# Pure_Keys_aec-pcb3-smd-inProgress.net
KiCad netlist of a schematic drawn in EAGLE
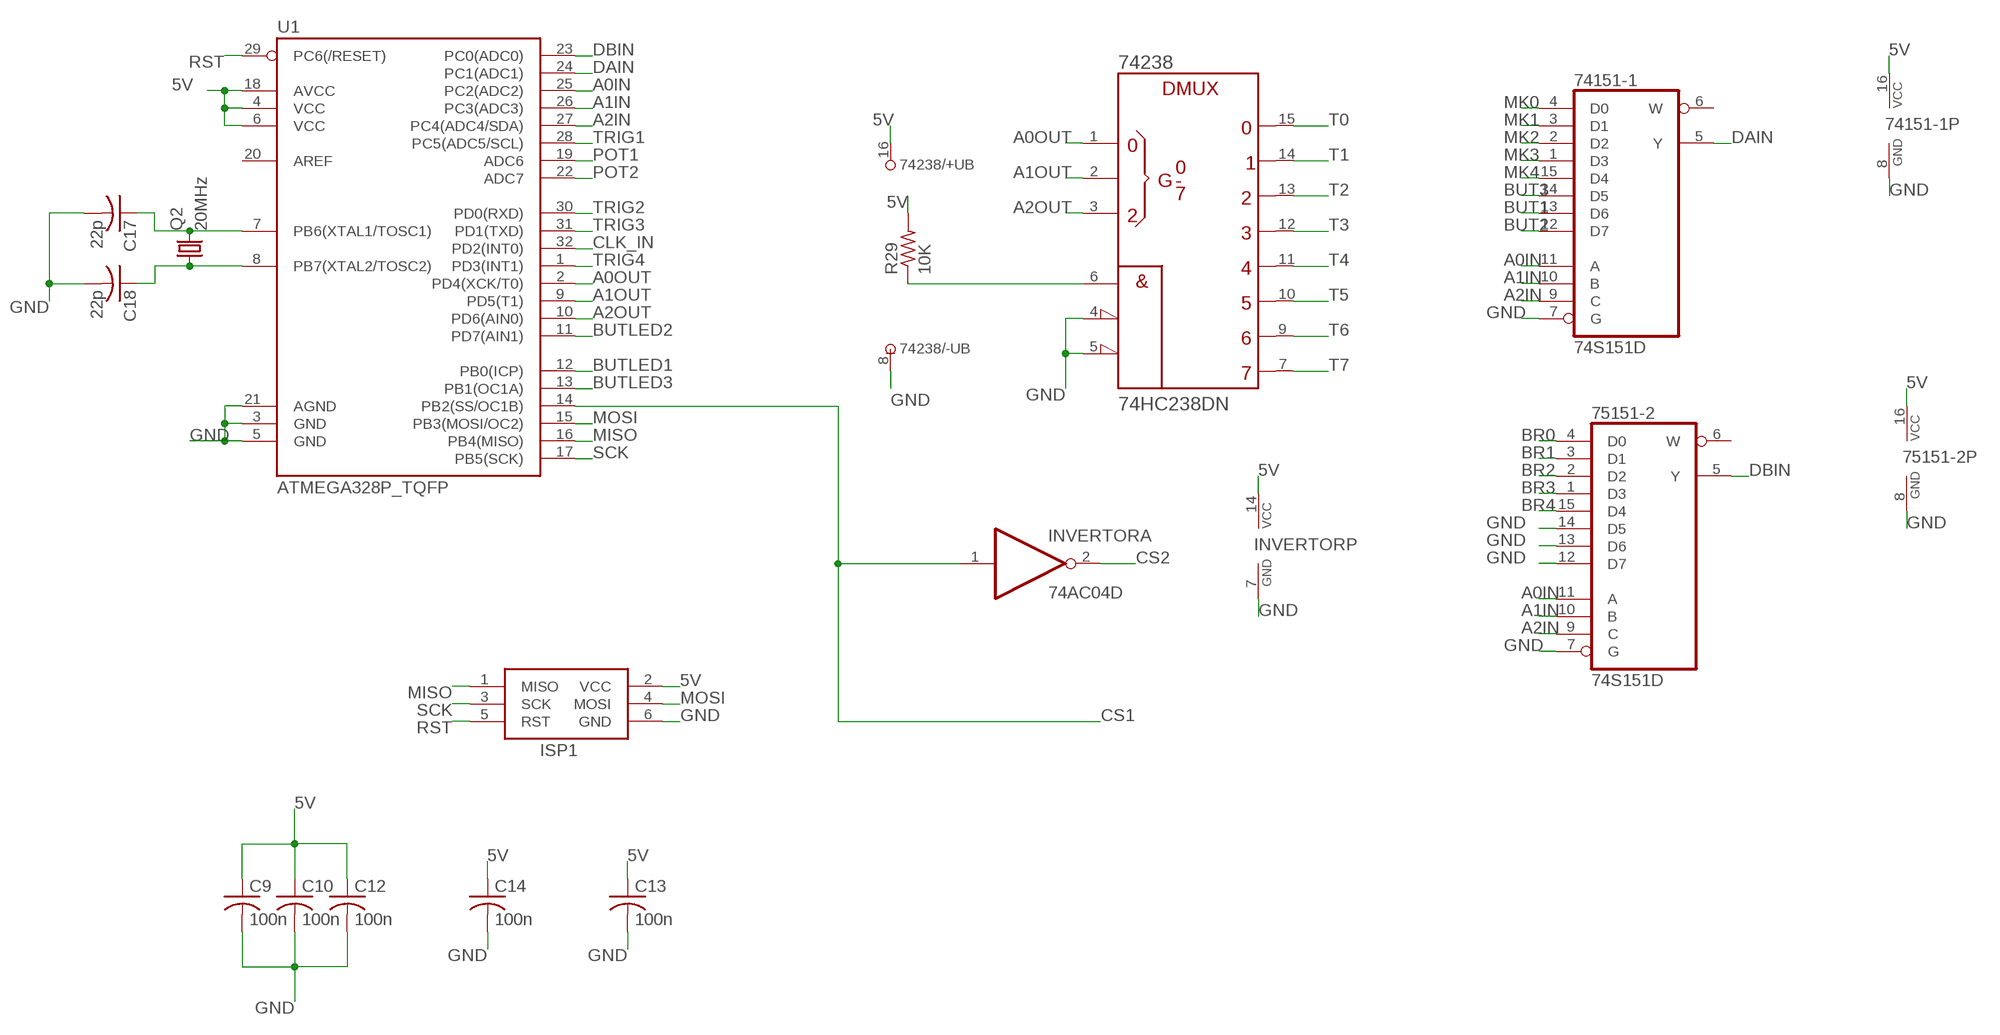
[diagram p0: schematic, sheet 1]
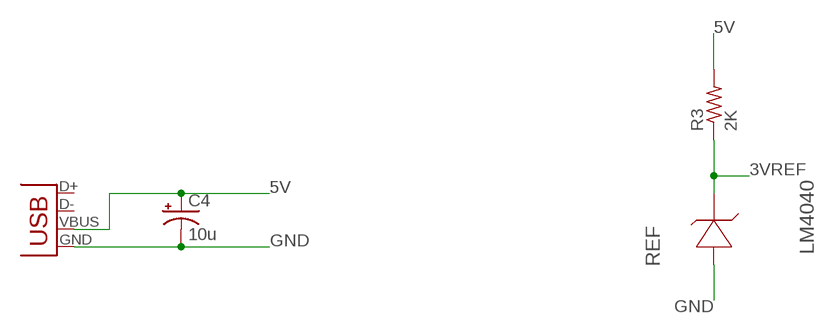
[diagram p1: schematic, sheet 2]
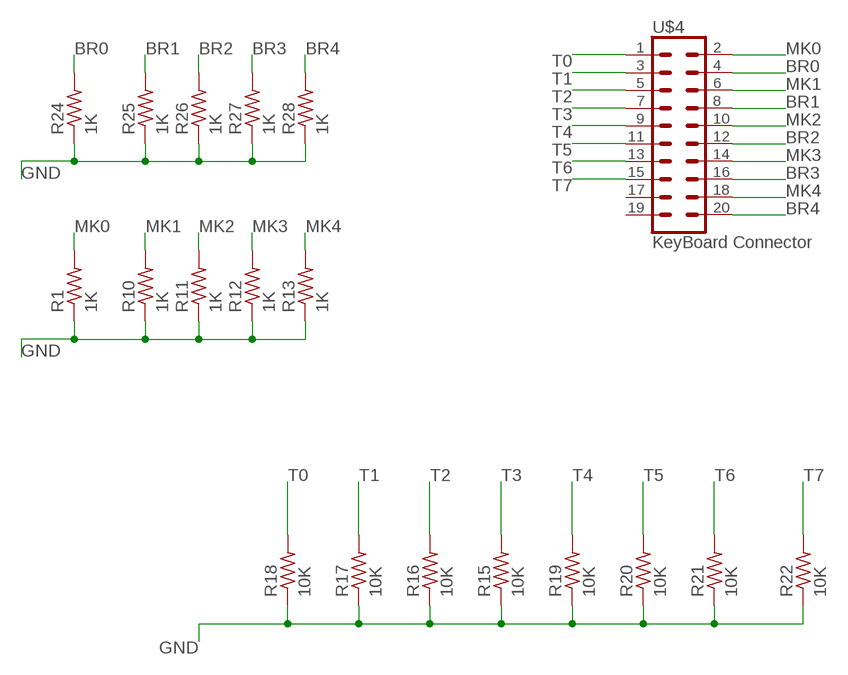
[diagram p2: schematic, sheet 3]
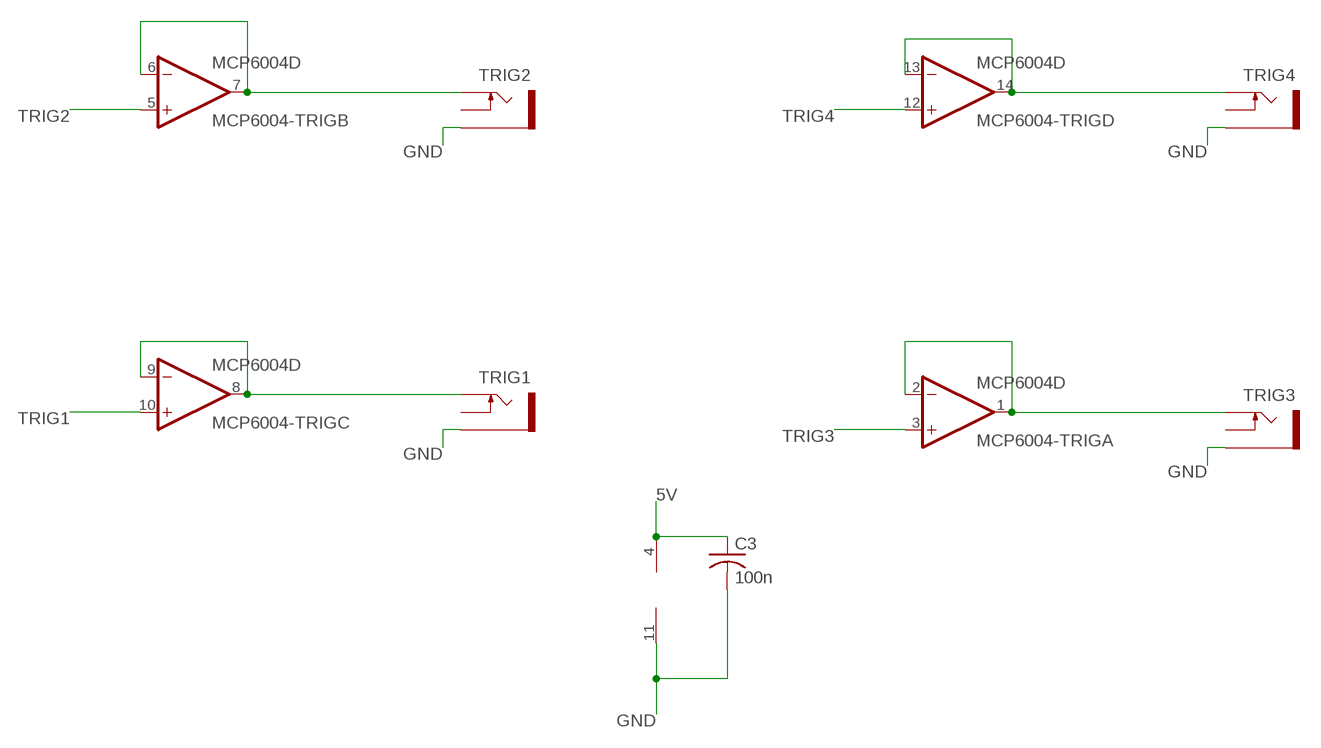
[diagram p3: schematic, sheet 4]
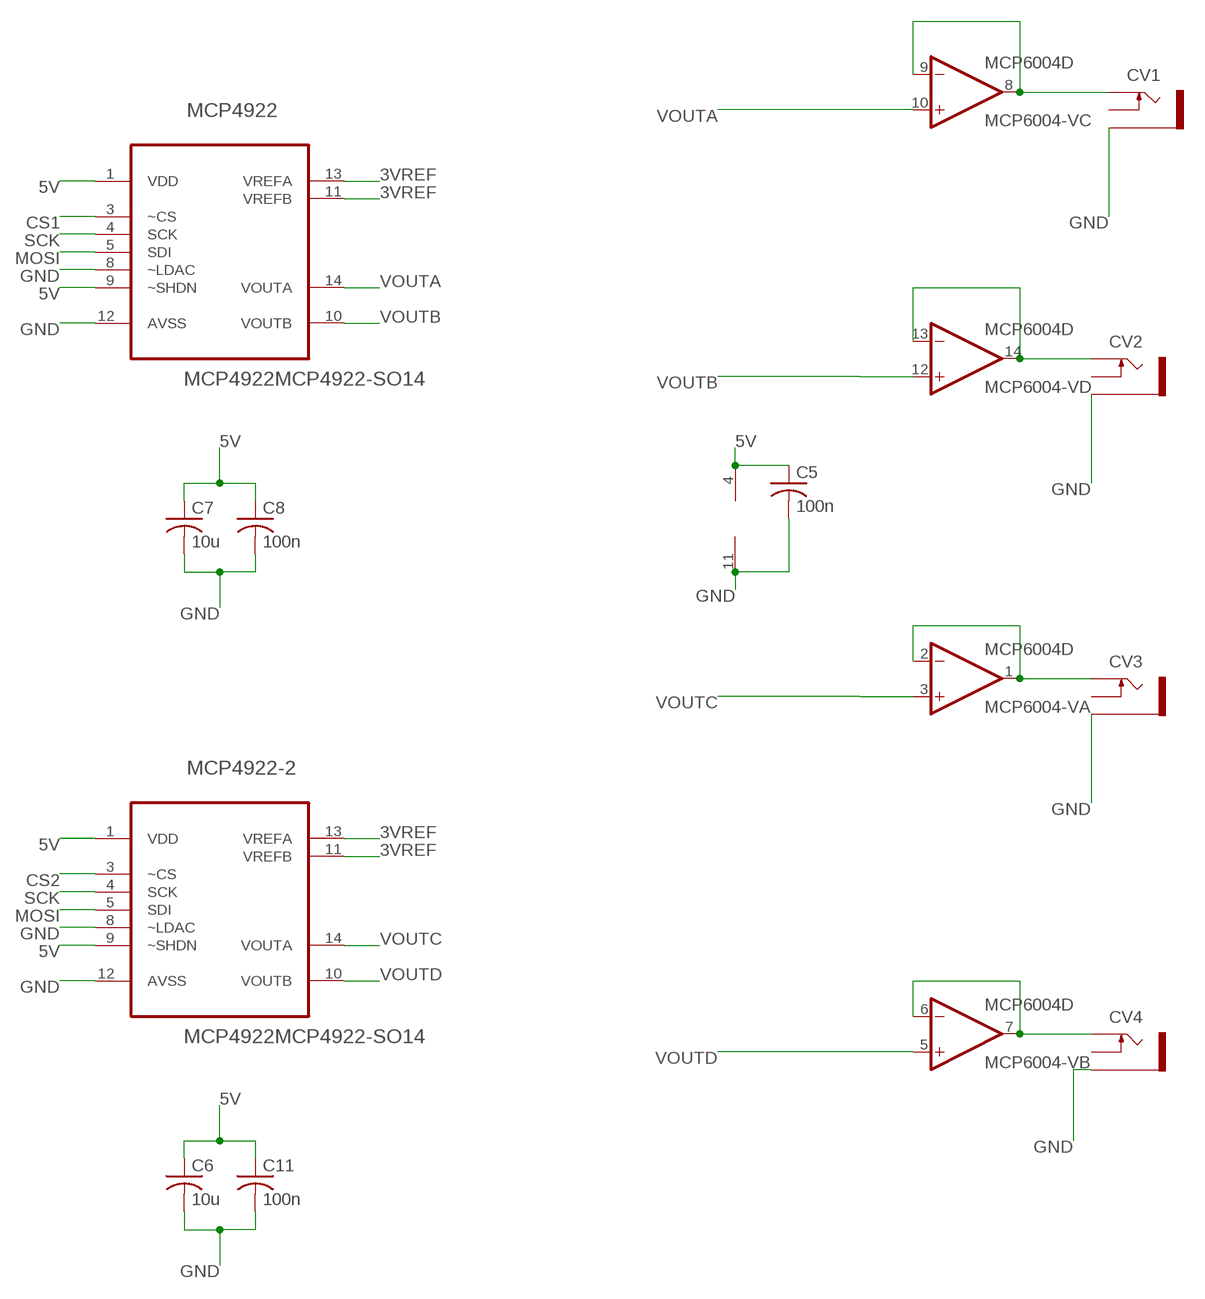
[diagram p4: schematic, sheet 5]
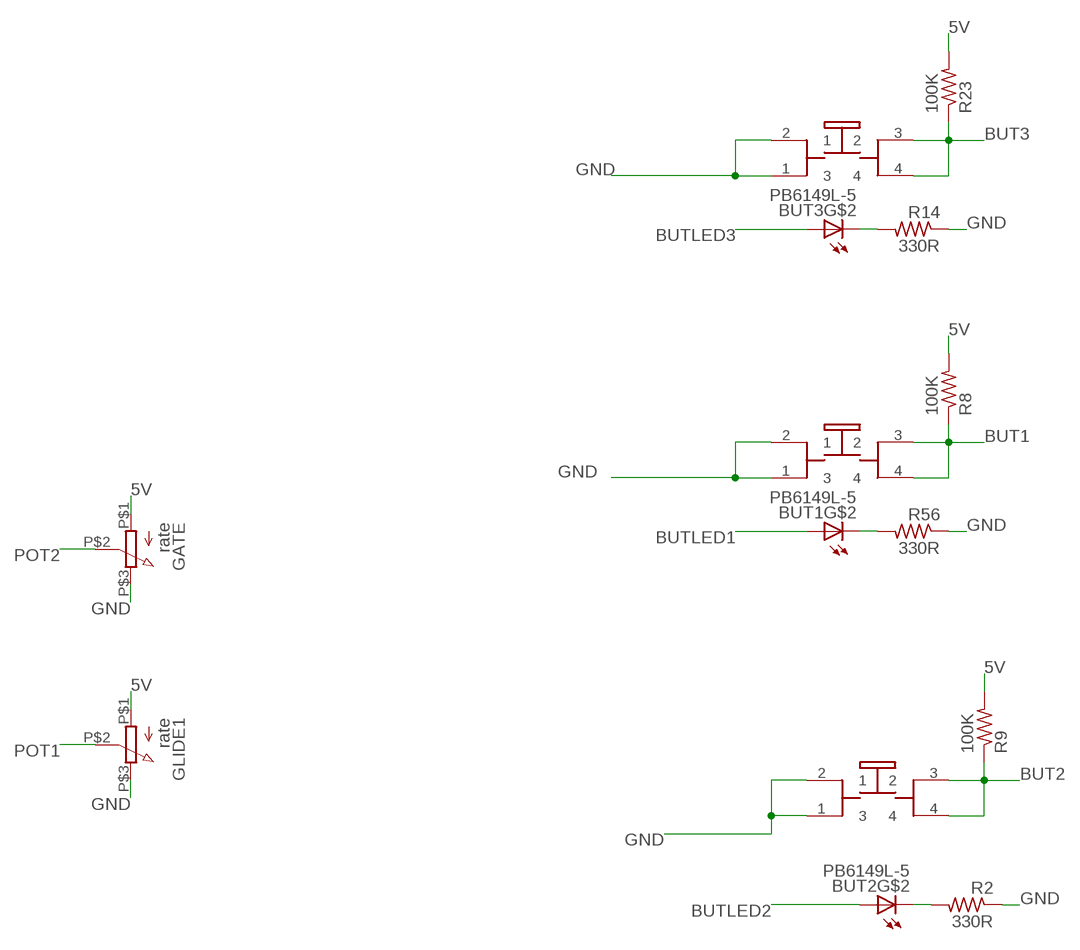
[diagram p5: schematic, sheet 6]
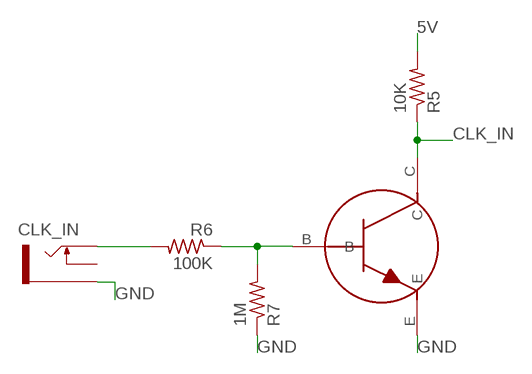
[diagram p6: schematic, sheet 7]

(export (version "E")
  (design (tool "Eeschema 10.0.6"))
  (components
    (comp (ref "C4")
      (value "10u")
      (footprint "eagle-import:153CLV-0505")
      (libsource (lib "eagle-import") (part "CPOL-US153CLV-0505"))
    )
    (comp (ref "JP2")
      (value "USB-B")
      (footprint "eagle-import:USB-B-PTH")
      (libsource (lib "eagle-import") (part "USBPTH"))
    )
    (comp (ref "R3")
      (value "2K")
      (footprint "eagle-import:R0805")
      (libsource (lib "eagle-import") (part "R-US_R0805"))
    )
    (comp (ref "REF")
      (value "LM4040")
      (footprint "eagle-import:SOT95P237X112-3N")
      (fields
        (field (name "MPN") "LM4040A50IDBZT")
        (field (name "MPN_1") "LM4040A30IDBZT")
        (field (name "RS-PART") "809-6343")
      )
      (libsource (lib "eagle-import") (part "LM4040A30IDBZT"))
    )
    (comp (ref "CLK_IN")
      (value "PJ302M")
      (footprint "eagle-import:PJ302M")
      (libsource (lib "eagle-import") (part "PJ302M"))
    )
    (comp (ref "CLOCK")
      (value "2N3904")
      (footprint "eagle-import:TRANSISTOR_SINGLE_N-TYPE")
      (libsource (lib "eagle-import") (part "TRANSISTOR_MMBT3904"))
    )
    (comp (ref "R5")
      (value "10K")
      (footprint "eagle-import:R0805")
      (libsource (lib "eagle-import") (part "R-US_R0805"))
    )
    (comp (ref "R6")
      (value "100K")
      (footprint "eagle-import:R0805")
      (libsource (lib "eagle-import") (part "R-US_R0805"))
    )
    (comp (ref "R7")
      (value "1M")
      (footprint "eagle-import:R0805")
      (libsource (lib "eagle-import") (part "R-US_R0805"))
    )
    (comp (ref "74151-1")
      (value "74S151D")
      (footprint "eagle-import:SO16")
      (libsource (lib "eagle-import") (part "74151DS"))
    )
    (comp (ref "74238")
      (value "74HC238DN")
      (footprint "eagle-import:SO16")
      (libsource (lib "eagle-import") (part "74HC238DN"))
    )
    (comp (ref "75151-2")
      (value "74S151D")
      (footprint "eagle-import:SO16")
      (libsource (lib "eagle-import") (part "74151DS"))
    )
    (comp (ref "C9")
      (value "100n")
      (footprint "eagle-import:C0805K")
      (libsource (lib "eagle-import") (part "C-USC0805K"))
    )
    (comp (ref "C10")
      (value "100n")
      (footprint "eagle-import:C0805K")
      (libsource (lib "eagle-import") (part "C-USC0805K"))
    )
    (comp (ref "C12")
      (value "100n")
      (footprint "eagle-import:C0805K")
      (libsource (lib "eagle-import") (part "C-USC0805K"))
    )
    (comp (ref "C13")
      (value "100n")
      (footprint "eagle-import:C0805K")
      (libsource (lib "eagle-import") (part "C-USC0805K"))
    )
    (comp (ref "C14")
      (value "100n")
      (footprint "eagle-import:C0805K")
      (libsource (lib "eagle-import") (part "C-USC0805K"))
    )
    (comp (ref "C17")
      (value "22p")
      (footprint "eagle-import:C0805K")
      (libsource (lib "eagle-import") (part "C-USC0805K"))
    )
    (comp (ref "C18")
      (value "22p")
      (footprint "eagle-import:C0805K")
      (libsource (lib "eagle-import") (part "C-USC0805K"))
    )
    (comp (ref "INVERTOR")
      (value "74AC04D")
      (footprint "eagle-import:SO14")
      (libsource (lib "eagle-import") (part "7404DAC"))
    )
    (comp (ref "ISP1")
      (value "AVRISP-6")
      (footprint "eagle-import:AVRISP")
      (libsource (lib "eagle-import") (part "AVRISP-6"))
    )
    (comp (ref "Q2")
      (value "20MHz")
      (footprint "eagle-import:HC49UP")
      (libsource (lib "eagle-import") (part "CRYSTALHC49UP"))
    )
    (comp (ref "R29")
      (value "10K")
      (footprint "eagle-import:R0805")
      (libsource (lib "eagle-import") (part "R-US_R0805"))
    )
    (comp (ref "U1")
      (value "ATMEGA328P_TQFP")
      (footprint "eagle-import:TQFP32-08")
      (libsource (lib "eagle-import") (part "ATMEGA328P_TQFP"))
    )
    (comp (ref "C5")
      (value "100n")
      (footprint "eagle-import:C0805K")
      (libsource (lib "eagle-import") (part "C-USC0805K"))
    )
    (comp (ref "C6")
      (value "10u")
      (footprint "eagle-import:C0805K")
      (libsource (lib "eagle-import") (part "C-USC0805K"))
    )
    (comp (ref "C7")
      (value "10u")
      (footprint "eagle-import:C0805K")
      (libsource (lib "eagle-import") (part "C-USC0805K"))
    )
    (comp (ref "C8")
      (value "100n")
      (footprint "eagle-import:C0805K")
      (libsource (lib "eagle-import") (part "C-USC0805K"))
    )
    (comp (ref "C11")
      (value "100n")
      (footprint "eagle-import:C0805K")
      (libsource (lib "eagle-import") (part "C-USC0805K"))
    )
    (comp (ref "CV1")
      (value "PJ302M")
      (footprint "eagle-import:PJ302M")
      (libsource (lib "eagle-import") (part "PJ302M"))
    )
    (comp (ref "CV2")
      (value "PJ302M")
      (footprint "eagle-import:PJ302M")
      (libsource (lib "eagle-import") (part "PJ302M"))
    )
    (comp (ref "CV3")
      (value "PJ302M")
      (footprint "eagle-import:PJ302M")
      (libsource (lib "eagle-import") (part "PJ302M"))
    )
    (comp (ref "CV4")
      (value "PJ302M")
      (footprint "eagle-import:PJ302M")
      (libsource (lib "eagle-import") (part "PJ302M"))
    )
    (comp (ref "MCP4922")
      (value "MCP4922MCP4922-SO14")
      (footprint "eagle-import:SO14")
      (libsource (lib "eagle-import") (part "MCP4922MCP4922-SO14"))
    )
    (comp (ref "MCP4922-2")
      (value "MCP4922MCP4922-SO14")
      (footprint "eagle-import:SO14")
      (libsource (lib "eagle-import") (part "MCP4922MCP4922-SO14"))
    )
    (comp (ref "MCP6004-V")
      (value "MCP6004D")
      (footprint "eagle-import:SO14")
      (libsource (lib "eagle-import") (part "MCP6004D"))
    )
    (comp (ref "BUT1")
      (value "PB6149L-5")
      (footprint "eagle-import:PB6149L")
      (libsource (lib "eagle-import") (part "PB6149L-5"))
    )
    (comp (ref "BUT2")
      (value "PB6149L-5")
      (footprint "eagle-import:PB6149L")
      (libsource (lib "eagle-import") (part "PB6149L-5"))
    )
    (comp (ref "BUT3")
      (value "PB6149L-5")
      (footprint "eagle-import:PB6149L")
      (libsource (lib "eagle-import") (part "PB6149L-5"))
    )
    (comp (ref "GATE")
      (value "rate")
      (footprint "eagle-import:POT")
      (libsource (lib "eagle-import") (part "9MMPOT"))
    )
    (comp (ref "GLIDE1")
      (value "rate")
      (footprint "eagle-import:POT")
      (libsource (lib "eagle-import") (part "9MMPOT"))
    )
    (comp (ref "R2")
      (value "330R")
      (footprint "eagle-import:R0805")
      (libsource (lib "eagle-import") (part "R-US_R0805"))
    )
    (comp (ref "R8")
      (value "100K")
      (footprint "eagle-import:R0805")
      (libsource (lib "eagle-import") (part "R-US_R0805"))
    )
    (comp (ref "R9")
      (value "100K")
      (footprint "eagle-import:R0805")
      (libsource (lib "eagle-import") (part "R-US_R0805"))
    )
    (comp (ref "R14")
      (value "330R")
      (footprint "eagle-import:R0805")
      (libsource (lib "eagle-import") (part "R-US_R0805"))
    )
    (comp (ref "R23")
      (value "100K")
      (footprint "eagle-import:R0805")
      (libsource (lib "eagle-import") (part "R-US_R0805"))
    )
    (comp (ref "R56")
      (value "330R")
      (footprint "eagle-import:R0805")
      (libsource (lib "eagle-import") (part "R-US_R0805"))
    )
    (comp (ref "R1")
      (value "1K")
      (footprint "eagle-import:R0805")
      (fields (field (name "RS-PART") "223-0427"))
      (libsource (lib "eagle-import") (part "R-US_R0805"))
    )
    (comp (ref "R10")
      (value "1K")
      (footprint "eagle-import:R0805")
      (fields (field (name "RS-PART") "223-0427"))
      (libsource (lib "eagle-import") (part "R-US_R0805"))
    )
    (comp (ref "R11")
      (value "1K")
      (footprint "eagle-import:R0805")
      (fields (field (name "RS-PART") "223-0427"))
      (libsource (lib "eagle-import") (part "R-US_R0805"))
    )
    (comp (ref "R12")
      (value "1K")
      (footprint "eagle-import:R0805")
      (fields (field (name "RS-PART") "223-0427"))
      (libsource (lib "eagle-import") (part "R-US_R0805"))
    )
    (comp (ref "R13")
      (value "1K")
      (footprint "eagle-import:R0805")
      (fields (field (name "RS-PART") "223-0427"))
      (libsource (lib "eagle-import") (part "R-US_R0805"))
    )
    (comp (ref "R15")
      (value "10K")
      (footprint "eagle-import:R0805")
      (libsource (lib "eagle-import") (part "R-US_R0805"))
    )
    (comp (ref "R16")
      (value "10K")
      (footprint "eagle-import:R0805")
      (libsource (lib "eagle-import") (part "R-US_R0805"))
    )
    (comp (ref "R17")
      (value "10K")
      (footprint "eagle-import:R0805")
      (libsource (lib "eagle-import") (part "R-US_R0805"))
    )
    (comp (ref "R18")
      (value "10K")
      (footprint "eagle-import:R0805")
      (libsource (lib "eagle-import") (part "R-US_R0805"))
    )
    (comp (ref "R19")
      (value "10K")
      (footprint "eagle-import:R0805")
      (libsource (lib "eagle-import") (part "R-US_R0805"))
    )
    (comp (ref "R20")
      (value "10K")
      (footprint "eagle-import:R0805")
      (libsource (lib "eagle-import") (part "R-US_R0805"))
    )
    (comp (ref "R21")
      (value "10K")
      (footprint "eagle-import:R0805")
      (libsource (lib "eagle-import") (part "R-US_R0805"))
    )
    (comp (ref "R22")
      (value "10K")
      (footprint "eagle-import:R0805")
      (libsource (lib "eagle-import") (part "R-US_R0805"))
    )
    (comp (ref "R24")
      (value "1K")
      (footprint "eagle-import:R0805")
      (fields (field (name "RS-PART") "223-0427"))
      (libsource (lib "eagle-import") (part "R-US_R0805"))
    )
    (comp (ref "R25")
      (value "1K")
      (footprint "eagle-import:R0805")
      (fields (field (name "RS-PART") "223-0427"))
      (libsource (lib "eagle-import") (part "R-US_R0805"))
    )
    (comp (ref "R26")
      (value "1K")
      (footprint "eagle-import:R0805")
      (fields (field (name "RS-PART") "223-0427"))
      (libsource (lib "eagle-import") (part "R-US_R0805"))
    )
    (comp (ref "R27")
      (value "1K")
      (footprint "eagle-import:R0805")
      (fields (field (name "RS-PART") "223-0427"))
      (libsource (lib "eagle-import") (part "R-US_R0805"))
    )
    (comp (ref "R28")
      (value "1K")
      (footprint "eagle-import:R0805")
      (fields (field (name "RS-PART") "223-0427"))
      (libsource (lib "eagle-import") (part "R-US_R0805"))
    )
    (comp (ref "U$4")
      (value "KeyBoard Connector")
      (footprint "eagle-import:2X10")
      (fields (field (name "RS-PART") "669-5364"))
      (libsource (lib "eagle-import") (part "CONN_10X2"))
    )
    (comp (ref "C3")
      (value "100n")
      (footprint "eagle-import:C0805K")
      (libsource (lib "eagle-import") (part "C-USC0805K"))
    )
    (comp (ref "MCP6004-TRIG")
      (value "MCP6004D")
      (footprint "eagle-import:SO14")
      (libsource (lib "eagle-import") (part "MCP6004D"))
    )
    (comp (ref "TRIG1")
      (value "PJ302M")
      (footprint "eagle-import:PJ302M")
      (libsource (lib "eagle-import") (part "PJ302M"))
    )
    (comp (ref "TRIG2")
      (value "PJ302M")
      (footprint "eagle-import:PJ302M")
      (libsource (lib "eagle-import") (part "PJ302M"))
    )
    (comp (ref "TRIG3")
      (value "PJ302M")
      (footprint "eagle-import:PJ302M")
      (libsource (lib "eagle-import") (part "PJ302M"))
    )
    (comp (ref "TRIG4")
      (value "PJ302M")
      (footprint "eagle-import:PJ302M")
      (libsource (lib "eagle-import") (part "PJ302M"))
    )
  )
  (nets
    (net (code "1") (name "3VREF") (class "Default")
      (node (ref "MCP4922") (pin "11") (pinfunction "VREFB_11") (pintype "bidirectional"))
      (node (ref "MCP4922") (pin "13") (pinfunction "VREFA_13") (pintype "input"))
      (node (ref "MCP4922-2") (pin "11") (pinfunction "VREFB_11") (pintype "bidirectional"))
      (node (ref "MCP4922-2") (pin "13") (pinfunction "VREFA_13") (pintype "input"))
      (node (ref "R3") (pin "1") (pinfunction "1_1") (pintype "passive"))
      (node (ref "REF") (pin "1") (pinfunction "CATHODE_1") (pintype "output"))
    )
    (net (code "2") (name "5V") (class "Default")
      (node (ref "74151-1") (pin "16") (pinfunction "VCC_16") (pintype "power_in"))
      (node (ref "74238") (pin "16") (pinfunction "+UB_16") (pintype "power_in"))
      (node (ref "75151-2") (pin "16") (pinfunction "VCC_16") (pintype "power_in"))
      (node (ref "C10") (pin "1") (pinfunction "1_1") (pintype "passive"))
      (node (ref "C11") (pin "1") (pinfunction "1_1") (pintype "passive"))
      (node (ref "C12") (pin "1") (pinfunction "1_1") (pintype "passive"))
      (node (ref "C13") (pin "1") (pinfunction "1_1") (pintype "passive"))
      (node (ref "C14") (pin "1") (pinfunction "1_1") (pintype "passive"))
      (node (ref "C3") (pin "1") (pinfunction "1_1") (pintype "passive"))
      (node (ref "C4") (pin "+") (pinfunction "+_+") (pintype "passive"))
      (node (ref "C5") (pin "1") (pinfunction "1_1") (pintype "passive"))
      (node (ref "C6") (pin "1") (pinfunction "1_1") (pintype "passive"))
      (node (ref "C7") (pin "1") (pinfunction "1_1") (pintype "passive"))
      (node (ref "C8") (pin "1") (pinfunction "1_1") (pintype "passive"))
      (node (ref "C9") (pin "1") (pinfunction "1_1") (pintype "passive"))
      (node (ref "GATE") (pin "P$1") (pinfunction "1_P$1") (pintype "passive"))
      (node (ref "GLIDE1") (pin "P$1") (pinfunction "1_P$1") (pintype "passive"))
      (node (ref "INVERTOR") (pin "14") (pinfunction "VCC_14") (pintype "power_in"))
      (node (ref "ISP1") (pin "2") (pinfunction "VCC_2") (pintype "power_in"))
      (node (ref "JP2") (pin "VBUS") (pinfunction "VBUS_VBUS") (pintype "bidirectional"))
      (node (ref "MCP4922") (pin "1") (pinfunction "VDD_1") (pintype "power_in"))
      (node (ref "MCP4922") (pin "9") (pinfunction "~{SHDN}_9") (pintype "bidirectional"))
      (node (ref "MCP4922-2") (pin "1") (pinfunction "VDD_1") (pintype "power_in"))
      (node (ref "MCP4922-2") (pin "9") (pinfunction "~{SHDN}_9") (pintype "bidirectional"))
      (node (ref "MCP6004-TRIG") (pin "4") (pinfunction "V+_4") (pintype "power_in"))
      (node (ref "MCP6004-V") (pin "4") (pinfunction "V+_4") (pintype "power_in"))
      (node (ref "R23") (pin "2") (pinfunction "2_2") (pintype "passive"))
      (node (ref "R29") (pin "2") (pinfunction "2_2") (pintype "passive"))
      (node (ref "R3") (pin "2") (pinfunction "2_2") (pintype "passive"))
      (node (ref "R5") (pin "2") (pinfunction "2_2") (pintype "passive"))
      (node (ref "R8") (pin "2") (pinfunction "2_2") (pintype "passive"))
      (node (ref "R9") (pin "2") (pinfunction "2_2") (pintype "passive"))
      (node (ref "U1") (pin "18") (pinfunction "AVCC_18") (pintype "bidirectional"))
      (node (ref "U1") (pin "4") (pinfunction "VCC_4") (pintype "bidirectional"))
      (node (ref "U1") (pin "6") (pinfunction "VCC_6") (pintype "bidirectional"))
    )
    (net (code "3") (name "A0IN") (class "Default")
      (node (ref "74151-1") (pin "11") (pinfunction "A_11") (pintype "input"))
      (node (ref "75151-2") (pin "11") (pinfunction "A_11") (pintype "input"))
      (node (ref "U1") (pin "25") (pinfunction "PC2(ADC2)_25") (pintype "bidirectional"))
    )
    (net (code "4") (name "A0OUT") (class "Default")
      (node (ref "74238") (pin "1") (pinfunction "A_1") (pintype "input"))
      (node (ref "U1") (pin "2") (pinfunction "PD4(XCK/T0)_2") (pintype "bidirectional"))
    )
    (net (code "5") (name "A1IN") (class "Default")
      (node (ref "74151-1") (pin "10") (pinfunction "B_10") (pintype "input"))
      (node (ref "75151-2") (pin "10") (pinfunction "B_10") (pintype "input"))
      (node (ref "U1") (pin "26") (pinfunction "PC3(ADC3)_26") (pintype "bidirectional"))
    )
    (net (code "6") (name "A1OUT") (class "Default")
      (node (ref "74238") (pin "2") (pinfunction "B_2") (pintype "input"))
      (node (ref "U1") (pin "9") (pinfunction "PD5(T1)_9") (pintype "bidirectional"))
    )
    (net (code "7") (name "A2IN") (class "Default")
      (node (ref "74151-1") (pin "9") (pinfunction "C_9") (pintype "input"))
      (node (ref "75151-2") (pin "9") (pinfunction "C_9") (pintype "input"))
      (node (ref "U1") (pin "27") (pinfunction "PC4(ADC4/SDA)_27") (pintype "bidirectional"))
    )
    (net (code "8") (name "A2OUT") (class "Default")
      (node (ref "74238") (pin "3") (pinfunction "C_3") (pintype "input"))
      (node (ref "U1") (pin "10") (pinfunction "PD6(AIN0)_10") (pintype "bidirectional"))
    )
    (net (code "9") (name "BR0") (class "Default")
      (node (ref "75151-2") (pin "4") (pinfunction "D0_4") (pintype "input"))
      (node (ref "R24") (pin "2") (pinfunction "2_2") (pintype "passive"))
      (node (ref "U$4") (pin "4") (pinfunction "4_4") (pintype "passive"))
    )
    (net (code "10") (name "BR1") (class "Default")
      (node (ref "75151-2") (pin "3") (pinfunction "D1_3") (pintype "input"))
      (node (ref "R25") (pin "2") (pinfunction "2_2") (pintype "passive"))
      (node (ref "U$4") (pin "8") (pinfunction "8_8") (pintype "passive"))
    )
    (net (code "11") (name "BR2") (class "Default")
      (node (ref "75151-2") (pin "2") (pinfunction "D2_2") (pintype "input"))
      (node (ref "R26") (pin "2") (pinfunction "2_2") (pintype "passive"))
      (node (ref "U$4") (pin "12") (pinfunction "12_12") (pintype "passive"))
    )
    (net (code "12") (name "BR3") (class "Default")
      (node (ref "75151-2") (pin "1") (pinfunction "D3_1") (pintype "input"))
      (node (ref "R27") (pin "2") (pinfunction "2_2") (pintype "passive"))
      (node (ref "U$4") (pin "16") (pinfunction "16_16") (pintype "passive"))
    )
    (net (code "13") (name "BR4") (class "Default")
      (node (ref "75151-2") (pin "15") (pinfunction "D4_15") (pintype "input"))
      (node (ref "R28") (pin "2") (pinfunction "2_2") (pintype "passive"))
      (node (ref "U$4") (pin "20") (pinfunction "20_20") (pintype "passive"))
    )
    (net (code "14") (name "BUT1") (class "Default")
      (node (ref "74151-1") (pin "13") (pinfunction "D6_13") (pintype "input"))
      (node (ref "BUT1") (pin "3") (pinfunction "2_3") (pintype "bidirectional"))
      (node (ref "BUT1") (pin "4") (pinfunction "4_4") (pintype "bidirectional"))
      (node (ref "R8") (pin "1") (pinfunction "1_1") (pintype "passive"))
    )
    (net (code "15") (name "BUT2") (class "Default")
      (node (ref "74151-1") (pin "12") (pinfunction "D7_12") (pintype "input"))
      (node (ref "BUT2") (pin "3") (pinfunction "2_3") (pintype "bidirectional"))
      (node (ref "BUT2") (pin "4") (pinfunction "4_4") (pintype "bidirectional"))
      (node (ref "R9") (pin "1") (pinfunction "1_1") (pintype "passive"))
    )
    (net (code "16") (name "BUT3") (class "Default")
      (node (ref "74151-1") (pin "14") (pinfunction "D5_14") (pintype "input"))
      (node (ref "BUT3") (pin "3") (pinfunction "2_3") (pintype "bidirectional"))
      (node (ref "BUT3") (pin "4") (pinfunction "4_4") (pintype "bidirectional"))
      (node (ref "R23") (pin "1") (pinfunction "1_1") (pintype "passive"))
    )
    (net (code "17") (name "BUTLED1") (class "Default")
      (node (ref "BUT1") (pin "A") (pinfunction "A_A") (pintype "passive"))
      (node (ref "U1") (pin "12") (pinfunction "PB0(ICP)_12") (pintype "bidirectional"))
    )
    (net (code "18") (name "BUTLED2") (class "Default")
      (node (ref "BUT2") (pin "A") (pinfunction "A_A") (pintype "passive"))
      (node (ref "U1") (pin "11") (pinfunction "PD7(AIN1)_11") (pintype "bidirectional"))
    )
    (net (code "19") (name "BUTLED3") (class "Default")
      (node (ref "BUT3") (pin "A") (pinfunction "A_A") (pintype "passive"))
      (node (ref "U1") (pin "13") (pinfunction "PB1(OC1A)_13") (pintype "bidirectional"))
    )
    (net (code "20") (name "CLK_IN") (class "Default")
      (node (ref "CLOCK") (pin "C") (pinfunction "C_C") (pintype "bidirectional"))
      (node (ref "R5") (pin "1") (pinfunction "1_1") (pintype "passive"))
      (node (ref "U1") (pin "32") (pinfunction "PD2(INT0)_32") (pintype "bidirectional"))
    )
    (net (code "21") (name "CS1") (class "Default")
      (node (ref "INVERTOR") (pin "1") (pinfunction "I_1") (pintype "input"))
      (node (ref "MCP4922") (pin "3") (pinfunction "~{CS}_3") (pintype "input"))
      (node (ref "U1") (pin "14") (pinfunction "PB2(SS/OC1B)_14") (pintype "bidirectional"))
    )
    (net (code "22") (name "CS2") (class "Default")
      (node (ref "INVERTOR") (pin "2") (pinfunction "O_2") (pintype "output"))
      (node (ref "MCP4922-2") (pin "3") (pinfunction "~{CS}_3") (pintype "input"))
    )
    (net (code "23") (name "DAIN") (class "Default")
      (node (ref "74151-1") (pin "5") (pinfunction "Y_5") (pintype "output"))
      (node (ref "U1") (pin "24") (pinfunction "PC1(ADC1)_24") (pintype "bidirectional"))
    )
    (net (code "24") (name "DBIN") (class "Default")
      (node (ref "75151-2") (pin "5") (pinfunction "Y_5") (pintype "output"))
      (node (ref "U1") (pin "23") (pinfunction "PC0(ADC0)_23") (pintype "bidirectional"))
    )
    (net (code "25") (name "GND") (class "Default")
      (node (ref "74151-1") (pin "7") (pinfunction "G_7") (pintype "input"))
      (node (ref "74151-1") (pin "8") (pinfunction "GND_8") (pintype "power_in"))
      (node (ref "74238") (pin "4") (pinfunction "~{G2A}_4") (pintype "input"))
      (node (ref "74238") (pin "5") (pinfunction "~{G2B}_5") (pintype "input"))
      (node (ref "74238") (pin "8") (pinfunction "-UB_8") (pintype "power_in"))
      (node (ref "75151-2") (pin "12") (pinfunction "D7_12") (pintype "input"))
      (node (ref "75151-2") (pin "13") (pinfunction "D6_13") (pintype "input"))
      (node (ref "75151-2") (pin "14") (pinfunction "D5_14") (pintype "input"))
      (node (ref "75151-2") (pin "7") (pinfunction "G_7") (pintype "input"))
      (node (ref "75151-2") (pin "8") (pinfunction "GND_8") (pintype "power_in"))
      (node (ref "BUT1") (pin "1") (pinfunction "3_1") (pintype "bidirectional"))
      (node (ref "BUT1") (pin "2") (pinfunction "1_2") (pintype "bidirectional"))
      (node (ref "BUT2") (pin "1") (pinfunction "3_1") (pintype "bidirectional"))
      (node (ref "BUT2") (pin "2") (pinfunction "1_2") (pintype "bidirectional"))
      (node (ref "BUT3") (pin "1") (pinfunction "3_1") (pintype "bidirectional"))
      (node (ref "BUT3") (pin "2") (pinfunction "1_2") (pintype "bidirectional"))
      (node (ref "C10") (pin "2") (pinfunction "2_2") (pintype "passive"))
      (node (ref "C11") (pin "2") (pinfunction "2_2") (pintype "passive"))
      (node (ref "C12") (pin "2") (pinfunction "2_2") (pintype "passive"))
      (node (ref "C13") (pin "2") (pinfunction "2_2") (pintype "passive"))
      (node (ref "C14") (pin "2") (pinfunction "2_2") (pintype "passive"))
      (node (ref "C17") (pin "2") (pinfunction "2_2") (pintype "passive"))
      (node (ref "C18") (pin "2") (pinfunction "2_2") (pintype "passive"))
      (node (ref "C3") (pin "2") (pinfunction "2_2") (pintype "passive"))
      (node (ref "C4") (pin "-") (pinfunction "-_-") (pintype "passive"))
      (node (ref "C5") (pin "2") (pinfunction "2_2") (pintype "passive"))
      (node (ref "C6") (pin "2") (pinfunction "2_2") (pintype "passive"))
      (node (ref "C7") (pin "2") (pinfunction "2_2") (pintype "passive"))
      (node (ref "C8") (pin "2") (pinfunction "2_2") (pintype "passive"))
      (node (ref "C9") (pin "2") (pinfunction "2_2") (pintype "passive"))
      (node (ref "CLK_IN") (pin "GND") (pinfunction "SLEEVE_GND") (pintype "passive"))
      (node (ref "CLOCK") (pin "E") (pinfunction "E_E") (pintype "bidirectional"))
      (node (ref "CV1") (pin "GND") (pinfunction "SLEEVE_GND") (pintype "passive"))
      (node (ref "CV2") (pin "GND") (pinfunction "SLEEVE_GND") (pintype "passive"))
      (node (ref "CV3") (pin "GND") (pinfunction "SLEEVE_GND") (pintype "passive"))
      (node (ref "CV4") (pin "GND") (pinfunction "SLEEVE_GND") (pintype "passive"))
      (node (ref "GATE") (pin "P$3") (pinfunction "3_P$3") (pintype "passive"))
      (node (ref "GLIDE1") (pin "P$3") (pinfunction "3_P$3") (pintype "passive"))
      (node (ref "INVERTOR") (pin "7") (pinfunction "GND_7") (pintype "power_in"))
      (node (ref "ISP1") (pin "6") (pinfunction "GND_6") (pintype "power_in"))
      (node (ref "JP2") (pin "GND") (pinfunction "GND_GND") (pintype "bidirectional"))
      (node (ref "MCP4922") (pin "12") (pinfunction "AVSS_12") (pintype "passive"))
      (node (ref "MCP4922") (pin "8") (pinfunction "~{LDAC}_8") (pintype "input"))
      (node (ref "MCP4922-2") (pin "12") (pinfunction "AVSS_12") (pintype "passive"))
      (node (ref "MCP4922-2") (pin "8") (pinfunction "~{LDAC}_8") (pintype "input"))
      (node (ref "MCP6004-TRIG") (pin "11") (pinfunction "V-_11") (pintype "power_in"))
      (node (ref "MCP6004-V") (pin "11") (pinfunction "V-_11") (pintype "power_in"))
      (node (ref "R1") (pin "1") (pinfunction "1_1") (pintype "passive"))
      (node (ref "R10") (pin "1") (pinfunction "1_1") (pintype "passive"))
      (node (ref "R11") (pin "1") (pinfunction "1_1") (pintype "passive"))
      (node (ref "R12") (pin "1") (pinfunction "1_1") (pintype "passive"))
      (node (ref "R13") (pin "1") (pinfunction "1_1") (pintype "passive"))
      (node (ref "R14") (pin "1") (pinfunction "1_1") (pintype "passive"))
      (node (ref "R15") (pin "1") (pinfunction "1_1") (pintype "passive"))
      (node (ref "R16") (pin "1") (pinfunction "1_1") (pintype "passive"))
      (node (ref "R17") (pin "1") (pinfunction "1_1") (pintype "passive"))
      (node (ref "R18") (pin "1") (pinfunction "1_1") (pintype "passive"))
      (node (ref "R19") (pin "1") (pinfunction "1_1") (pintype "passive"))
      (node (ref "R2") (pin "1") (pinfunction "1_1") (pintype "passive"))
      (node (ref "R20") (pin "1") (pinfunction "1_1") (pintype "passive"))
      (node (ref "R21") (pin "1") (pinfunction "1_1") (pintype "passive"))
      (node (ref "R22") (pin "1") (pinfunction "1_1") (pintype "passive"))
      (node (ref "R24") (pin "1") (pinfunction "1_1") (pintype "passive"))
      (node (ref "R25") (pin "1") (pinfunction "1_1") (pintype "passive"))
      (node (ref "R26") (pin "1") (pinfunction "1_1") (pintype "passive"))
      (node (ref "R27") (pin "1") (pinfunction "1_1") (pintype "passive"))
      (node (ref "R28") (pin "1") (pinfunction "1_1") (pintype "passive"))
      (node (ref "R56") (pin "1") (pinfunction "1_1") (pintype "passive"))
      (node (ref "R7") (pin "1") (pinfunction "1_1") (pintype "passive"))
      (node (ref "REF") (pin "2") (pinfunction "ANODE_2") (pintype "input"))
      (node (ref "TRIG1") (pin "GND") (pinfunction "SLEEVE_GND") (pintype "passive"))
      (node (ref "TRIG2") (pin "GND") (pinfunction "SLEEVE_GND") (pintype "passive"))
      (node (ref "TRIG3") (pin "GND") (pinfunction "SLEEVE_GND") (pintype "passive"))
      (node (ref "TRIG4") (pin "GND") (pinfunction "SLEEVE_GND") (pintype "passive"))
      (node (ref "U1") (pin "21") (pinfunction "AGND_21") (pintype "bidirectional"))
      (node (ref "U1") (pin "3") (pinfunction "GND_3") (pintype "bidirectional"))
      (node (ref "U1") (pin "5") (pinfunction "GND_5") (pintype "bidirectional"))
    )
    (net (code "26") (name "MISO") (class "Default")
      (node (ref "ISP1") (pin "1") (pinfunction "MISO_1") (pintype "input"))
      (node (ref "U1") (pin "16") (pinfunction "PB4(MISO)_16") (pintype "bidirectional"))
    )
    (net (code "27") (name "MK0") (class "Default")
      (node (ref "74151-1") (pin "4") (pinfunction "D0_4") (pintype "input"))
      (node (ref "R1") (pin "2") (pinfunction "2_2") (pintype "passive"))
      (node (ref "U$4") (pin "2") (pinfunction "2_2") (pintype "passive"))
    )
    (net (code "28") (name "MK1") (class "Default")
      (node (ref "74151-1") (pin "3") (pinfunction "D1_3") (pintype "input"))
      (node (ref "R10") (pin "2") (pinfunction "2_2") (pintype "passive"))
      (node (ref "U$4") (pin "6") (pinfunction "6_6") (pintype "passive"))
    )
    (net (code "29") (name "MK2") (class "Default")
      (node (ref "74151-1") (pin "2") (pinfunction "D2_2") (pintype "input"))
      (node (ref "R11") (pin "2") (pinfunction "2_2") (pintype "passive"))
      (node (ref "U$4") (pin "10") (pinfunction "10_10") (pintype "passive"))
    )
    (net (code "30") (name "MK3") (class "Default")
      (node (ref "74151-1") (pin "1") (pinfunction "D3_1") (pintype "input"))
      (node (ref "R12") (pin "2") (pinfunction "2_2") (pintype "passive"))
      (node (ref "U$4") (pin "14") (pinfunction "14_14") (pintype "passive"))
    )
    (net (code "31") (name "MK4") (class "Default")
      (node (ref "74151-1") (pin "15") (pinfunction "D4_15") (pintype "input"))
      (node (ref "R13") (pin "2") (pinfunction "2_2") (pintype "passive"))
      (node (ref "U$4") (pin "18") (pinfunction "18_18") (pintype "passive"))
    )
    (net (code "32") (name "MOSI") (class "Default")
      (node (ref "ISP1") (pin "4") (pinfunction "MOSI_4") (pintype "output"))
      (node (ref "MCP4922") (pin "5") (pinfunction "SDI_5") (pintype "input"))
      (node (ref "MCP4922-2") (pin "5") (pinfunction "SDI_5") (pintype "input"))
      (node (ref "U1") (pin "15") (pinfunction "PB3(MOSI/OC2)_15") (pintype "bidirectional"))
    )
    (net (code "33") (name "Net-(74238C-G1)") (class "Default")
      (node (ref "74238") (pin "6") (pinfunction "G1_6") (pintype "input"))
      (node (ref "R29") (pin "1") (pinfunction "1_1") (pintype "passive"))
    )
    (net (code "34") (name "Net-(BUT1B-C)") (class "Default")
      (node (ref "BUT1") (pin "K") (pinfunction "C_K") (pintype "passive"))
      (node (ref "R56") (pin "2") (pinfunction "2_2") (pintype "passive"))
    )
    (net (code "35") (name "Net-(BUT2B-C)") (class "Default")
      (node (ref "BUT2") (pin "K") (pinfunction "C_K") (pintype "passive"))
      (node (ref "R2") (pin "2") (pinfunction "2_2") (pintype "passive"))
    )
    (net (code "36") (name "Net-(BUT3B-C)") (class "Default")
      (node (ref "BUT3") (pin "K") (pinfunction "C_K") (pintype "passive"))
      (node (ref "R14") (pin "2") (pinfunction "2_2") (pintype "passive"))
    )
    (net (code "37") (name "Net-(CLK_IN-PadTIP)") (class "Default")
      (node (ref "CLK_IN") (pin "TIP") (pinfunction "TIP_TIP") (pintype "passive"))
      (node (ref "R6") (pin "2") (pinfunction "2_2") (pintype "passive"))
    )
    (net (code "38") (name "Net-(CLOCK-PadB)") (class "Default")
      (node (ref "CLOCK") (pin "B") (pinfunction "B_B") (pintype "bidirectional"))
      (node (ref "R6") (pin "1") (pinfunction "1_1") (pintype "passive"))
      (node (ref "R7") (pin "2") (pinfunction "2_2") (pintype "passive"))
    )
    (net (code "39") (name "Net-(MCP6004-TRIGA--IN)") (class "Default")
      (node (ref "MCP6004-TRIG") (pin "1") (pinfunction "OUT_1") (pintype "output"))
      (node (ref "MCP6004-TRIG") (pin "2") (pinfunction "-IN_2") (pintype "input"))
      (node (ref "TRIG3") (pin "TIP") (pinfunction "TIP_TIP") (pintype "passive"))
    )
    (net (code "40") (name "Net-(MCP6004-TRIGB--IN)") (class "Default")
      (node (ref "MCP6004-TRIG") (pin "6") (pinfunction "-IN_6") (pintype "input"))
      (node (ref "MCP6004-TRIG") (pin "7") (pinfunction "OUT_7") (pintype "output"))
      (node (ref "TRIG2") (pin "TIP") (pinfunction "TIP_TIP") (pintype "passive"))
    )
    (net (code "41") (name "Net-(MCP6004-TRIGC--IN)") (class "Default")
      (node (ref "MCP6004-TRIG") (pin "8") (pinfunction "OUT_8") (pintype "output"))
      (node (ref "MCP6004-TRIG") (pin "9") (pinfunction "-IN_9") (pintype "input"))
      (node (ref "TRIG1") (pin "TIP") (pinfunction "TIP_TIP") (pintype "passive"))
    )
    (net (code "42") (name "Net-(MCP6004-TRIGD--IN)") (class "Default")
      (node (ref "MCP6004-TRIG") (pin "13") (pinfunction "-IN_13") (pintype "input"))
      (node (ref "MCP6004-TRIG") (pin "14") (pinfunction "OUT_14") (pintype "output"))
      (node (ref "TRIG4") (pin "TIP") (pinfunction "TIP_TIP") (pintype "passive"))
    )
    (net (code "43") (name "Net-(MCP6004-VA--IN)") (class "Default")
      (node (ref "CV3") (pin "TIP") (pinfunction "TIP_TIP") (pintype "passive"))
      (node (ref "MCP6004-V") (pin "1") (pinfunction "OUT_1") (pintype "output"))
      (node (ref "MCP6004-V") (pin "2") (pinfunction "-IN_2") (pintype "input"))
    )
    (net (code "44") (name "Net-(MCP6004-VB--IN)") (class "Default")
      (node (ref "CV4") (pin "TIP") (pinfunction "TIP_TIP") (pintype "passive"))
      (node (ref "MCP6004-V") (pin "6") (pinfunction "-IN_6") (pintype "input"))
      (node (ref "MCP6004-V") (pin "7") (pinfunction "OUT_7") (pintype "output"))
    )
    (net (code "45") (name "Net-(MCP6004-VC--IN)") (class "Default")
      (node (ref "CV1") (pin "TIP") (pinfunction "TIP_TIP") (pintype "passive"))
      (node (ref "MCP6004-V") (pin "8") (pinfunction "OUT_8") (pintype "output"))
      (node (ref "MCP6004-V") (pin "9") (pinfunction "-IN_9") (pintype "input"))
    )
    (net (code "46") (name "Net-(MCP6004-VD--IN)") (class "Default")
      (node (ref "CV2") (pin "TIP") (pinfunction "TIP_TIP") (pintype "passive"))
      (node (ref "MCP6004-V") (pin "13") (pinfunction "-IN_13") (pintype "input"))
      (node (ref "MCP6004-V") (pin "14") (pinfunction "OUT_14") (pintype "output"))
    )
    (net (code "47") (name "Net-(U1-PB6(XTAL1{slash}TOSC1))") (class "Default")
      (node (ref "C17") (pin "1") (pinfunction "1_1") (pintype "passive"))
      (node (ref "Q2") (pin "2") (pinfunction "2_2") (pintype "passive"))
      (node (ref "U1") (pin "7") (pinfunction "PB6(XTAL1/TOSC1)_7") (pintype "bidirectional"))
    )
    (net (code "48") (name "Net-(U1-PB7(XTAL2{slash}TOSC2))") (class "Default")
      (node (ref "C18") (pin "1") (pinfunction "1_1") (pintype "passive"))
      (node (ref "Q2") (pin "1") (pinfunction "1_1") (pintype "passive"))
      (node (ref "U1") (pin "8") (pinfunction "PB7(XTAL2/TOSC2)_8") (pintype "bidirectional"))
    )
    (net (code "49") (name "POT1") (class "Default")
      (node (ref "GLIDE1") (pin "P$2") (pinfunction "2_P$2") (pintype "passive"))
      (node (ref "U1") (pin "19") (pinfunction "ADC6_19") (pintype "bidirectional"))
    )
    (net (code "50") (name "POT2") (class "Default")
      (node (ref "GATE") (pin "P$2") (pinfunction "2_P$2") (pintype "passive"))
      (node (ref "U1") (pin "22") (pinfunction "ADC7_22") (pintype "bidirectional"))
    )
    (net (code "51") (name "RST") (class "Default")
      (node (ref "ISP1") (pin "5") (pinfunction "RST_5") (pintype "output"))
      (node (ref "U1") (pin "29") (pinfunction "PC6(/RESET)_29") (pintype "bidirectional"))
    )
    (net (code "52") (name "SCK") (class "Default")
      (node (ref "ISP1") (pin "3") (pinfunction "SCK_3") (pintype "output"))
      (node (ref "MCP4922") (pin "4") (pinfunction "SCK_4") (pintype "input"))
      (node (ref "MCP4922-2") (pin "4") (pinfunction "SCK_4") (pintype "input"))
      (node (ref "U1") (pin "17") (pinfunction "PB5(SCK)_17") (pintype "bidirectional"))
    )
    (net (code "53") (name "T0") (class "Default")
      (node (ref "74238") (pin "15") (pinfunction "Y0_15") (pintype "output"))
      (node (ref "R18") (pin "2") (pinfunction "2_2") (pintype "passive"))
      (node (ref "U$4") (pin "1") (pinfunction "1_1") (pintype "passive"))
    )
    (net (code "54") (name "T1") (class "Default")
      (node (ref "74238") (pin "14") (pinfunction "Y1_14") (pintype "output"))
      (node (ref "R17") (pin "2") (pinfunction "2_2") (pintype "passive"))
      (node (ref "U$4") (pin "3") (pinfunction "3_3") (pintype "passive"))
    )
    (net (code "55") (name "T2") (class "Default")
      (node (ref "74238") (pin "13") (pinfunction "Y2_13") (pintype "output"))
      (node (ref "R16") (pin "2") (pinfunction "2_2") (pintype "passive"))
      (node (ref "U$4") (pin "5") (pinfunction "5_5") (pintype "passive"))
    )
    (net (code "56") (name "T3") (class "Default")
      (node (ref "74238") (pin "12") (pinfunction "Y3_12") (pintype "output"))
      (node (ref "R15") (pin "2") (pinfunction "2_2") (pintype "passive"))
      (node (ref "U$4") (pin "7") (pinfunction "7_7") (pintype "passive"))
    )
    (net (code "57") (name "T4") (class "Default")
      (node (ref "74238") (pin "11") (pinfunction "Y4_11") (pintype "output"))
      (node (ref "R19") (pin "2") (pinfunction "2_2") (pintype "passive"))
      (node (ref "U$4") (pin "9") (pinfunction "9_9") (pintype "passive"))
    )
    (net (code "58") (name "T5") (class "Default")
      (node (ref "74238") (pin "10") (pinfunction "Y5_10") (pintype "output"))
      (node (ref "R20") (pin "2") (pinfunction "2_2") (pintype "passive"))
      (node (ref "U$4") (pin "11") (pinfunction "11_11") (pintype "passive"))
    )
    (net (code "59") (name "T6") (class "Default")
      (node (ref "74238") (pin "9") (pinfunction "Y6_9") (pintype "output"))
      (node (ref "R21") (pin "2") (pinfunction "2_2") (pintype "passive"))
      (node (ref "U$4") (pin "13") (pinfunction "13_13") (pintype "passive"))
    )
    (net (code "60") (name "T7") (class "Default")
      (node (ref "74238") (pin "7") (pinfunction "Y7_7") (pintype "output"))
      (node (ref "R22") (pin "2") (pinfunction "2_2") (pintype "passive"))
      (node (ref "U$4") (pin "15") (pinfunction "15_15") (pintype "passive"))
    )
    (net (code "61") (name "TRIG1") (class "Default")
      (node (ref "MCP6004-TRIG") (pin "10") (pinfunction "+IN_10") (pintype "input"))
      (node (ref "U1") (pin "28") (pinfunction "PC5(ADC5/SCL)_28") (pintype "bidirectional"))
    )
    (net (code "62") (name "TRIG2") (class "Default")
      (node (ref "MCP6004-TRIG") (pin "5") (pinfunction "+IN_5") (pintype "input"))
      (node (ref "U1") (pin "30") (pinfunction "PD0(RXD)_30") (pintype "bidirectional"))
    )
    (net (code "63") (name "TRIG3") (class "Default")
      (node (ref "MCP6004-TRIG") (pin "3") (pinfunction "+IN_3") (pintype "input"))
      (node (ref "U1") (pin "31") (pinfunction "PD1(TXD)_31") (pintype "bidirectional"))
    )
    (net (code "64") (name "TRIG4") (class "Default")
      (node (ref "MCP6004-TRIG") (pin "12") (pinfunction "+IN_12") (pintype "input"))
      (node (ref "U1") (pin "1") (pinfunction "PD3(INT1)_1") (pintype "bidirectional"))
    )
    (net (code "65") (name "VOUTA") (class "Default")
      (node (ref "MCP4922") (pin "14") (pinfunction "VOUTA_14") (pintype "output"))
      (node (ref "MCP6004-V") (pin "10") (pinfunction "+IN_10") (pintype "input"))
    )
    (net (code "66") (name "VOUTB") (class "Default")
      (node (ref "MCP4922") (pin "10") (pinfunction "VOUTB_10") (pintype "output"))
      (node (ref "MCP6004-V") (pin "12") (pinfunction "+IN_12") (pintype "input"))
    )
    (net (code "67") (name "VOUTC") (class "Default")
      (node (ref "MCP4922-2") (pin "14") (pinfunction "VOUTA_14") (pintype "output"))
      (node (ref "MCP6004-V") (pin "3") (pinfunction "+IN_3") (pintype "input"))
    )
    (net (code "68") (name "VOUTD") (class "Default")
      (node (ref "MCP4922-2") (pin "10") (pinfunction "VOUTB_10") (pintype "output"))
      (node (ref "MCP6004-V") (pin "5") (pinfunction "+IN_5") (pintype "input"))
    )
    (net (code "69") (name "unconnected-(74151-1A-W-Pad6)") (class "Default")
      (node (ref "74151-1") (pin "6") (pinfunction "W_6") (pintype "output"))
    )
    (net (code "70") (name "unconnected-(75151-2A-W-Pad6)") (class "Default")
      (node (ref "75151-2") (pin "6") (pinfunction "W_6") (pintype "output"))
    )
    (net (code "71") (name "unconnected-(CLK_IN-SWITCH-PadSW)") (class "Default")
      (node (ref "CLK_IN") (pin "SW") (pinfunction "SWITCH_SW") (pintype "passive"))
    )
    (net (code "72") (name "unconnected-(CV1-SWITCH-PadSW)") (class "Default")
      (node (ref "CV1") (pin "SW") (pinfunction "SWITCH_SW") (pintype "passive"))
    )
    (net (code "73") (name "unconnected-(CV2-SWITCH-PadSW)") (class "Default")
      (node (ref "CV2") (pin "SW") (pinfunction "SWITCH_SW") (pintype "passive"))
    )
    (net (code "74") (name "unconnected-(CV3-SWITCH-PadSW)") (class "Default")
      (node (ref "CV3") (pin "SW") (pinfunction "SWITCH_SW") (pintype "passive"))
    )
    (net (code "75") (name "unconnected-(CV4-SWITCH-PadSW)") (class "Default")
      (node (ref "CV4") (pin "SW") (pinfunction "SWITCH_SW") (pintype "passive"))
    )
    (net (code "76") (name "unconnected-(JP2-PadD+)") (class "Default")
      (node (ref "JP2") (pin "D+") (pinfunction "D+_D+") (pintype "bidirectional"))
    )
    (net (code "77") (name "unconnected-(JP2-PadD-)") (class "Default")
      (node (ref "JP2") (pin "D-") (pinfunction "D-_D-") (pintype "bidirectional"))
    )
    (net (code "78") (name "unconnected-(REF-NC-Pad3)") (class "Default")
      (node (ref "REF") (pin "3") (pinfunction "NC_3") (pintype "no_connect"))
    )
    (net (code "79") (name "unconnected-(TRIG1-SWITCH-PadSW)") (class "Default")
      (node (ref "TRIG1") (pin "SW") (pinfunction "SWITCH_SW") (pintype "passive"))
    )
    (net (code "80") (name "unconnected-(TRIG2-SWITCH-PadSW)") (class "Default")
      (node (ref "TRIG2") (pin "SW") (pinfunction "SWITCH_SW") (pintype "passive"))
    )
    (net (code "81") (name "unconnected-(TRIG3-SWITCH-PadSW)") (class "Default")
      (node (ref "TRIG3") (pin "SW") (pinfunction "SWITCH_SW") (pintype "passive"))
    )
    (net (code "82") (name "unconnected-(TRIG4-SWITCH-PadSW)") (class "Default")
      (node (ref "TRIG4") (pin "SW") (pinfunction "SWITCH_SW") (pintype "passive"))
    )
    (net (code "83") (name "unconnected-(U$4-Pad17)") (class "Default")
      (node (ref "U$4") (pin "17") (pinfunction "17_17") (pintype "passive"))
    )
    (net (code "84") (name "unconnected-(U$4-Pad19)") (class "Default")
      (node (ref "U$4") (pin "19") (pinfunction "19_19") (pintype "passive"))
    )
    (net (code "85") (name "unconnected-(U1-AREF-Pad20)") (class "Default")
      (node (ref "U1") (pin "20") (pinfunction "AREF_20") (pintype "bidirectional"))
    )
  )
)
